# Mcontr_2.net
KiCad netlist of a schematic drawn in Altium Designer
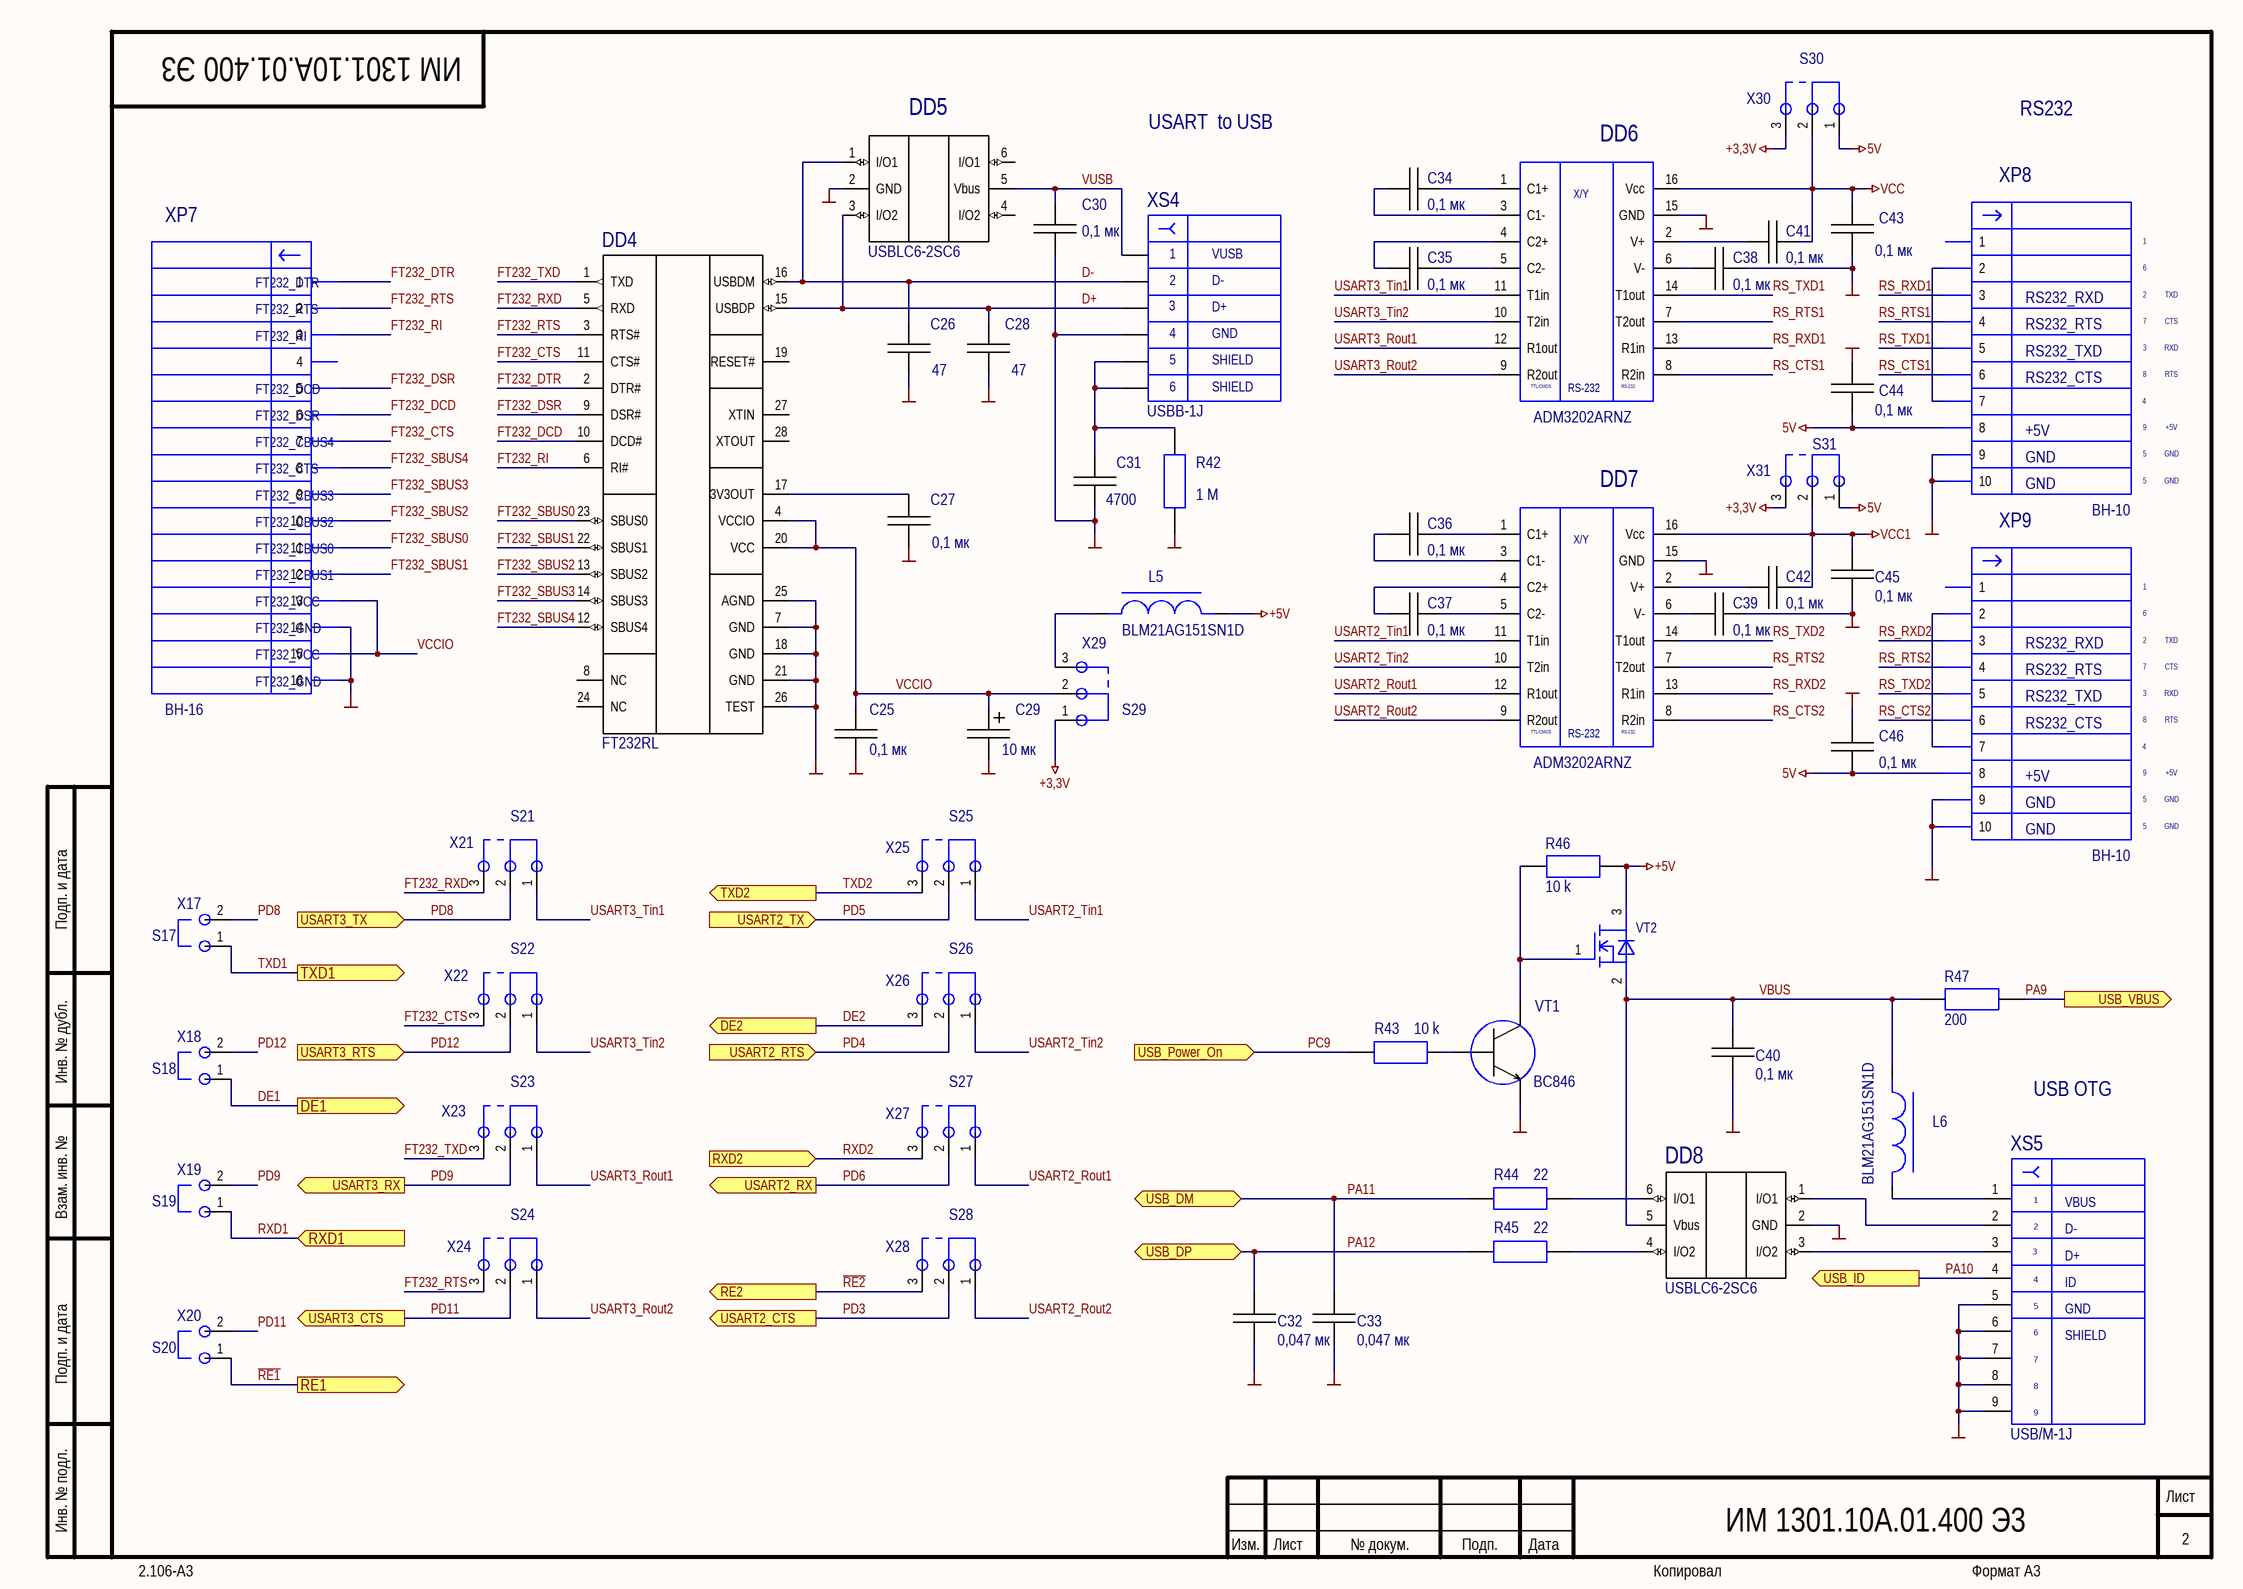
[diagram p0: Mcontr_2.SchDoc]

(export (version "E")
  (design (tool "Eeschema 10.0.6"))
  (components
    (comp (ref "C25")
      (value "0,1 мк")
      (footprint "CAPC_1206")
      (description "Capasitor")
      (fields (field (name "PART NUMBER") "C"))
      (libsource (lib "RLC_GOST") (part "C"))
    )
    (comp (ref "C26")
      (value "47")
      (footprint "CAPC_1206")
      (description "Capasitor")
      (fields (field (name "PART NUMBER") "C"))
      (libsource (lib "RLC_GOST") (part "C"))
    )
    (comp (ref "C27")
      (value "0,1 мк")
      (footprint "CAPC_1206")
      (description "Capasitor")
      (fields (field (name "PART NUMBER") "C"))
      (libsource (lib "RLC_GOST") (part "C"))
    )
    (comp (ref "C28")
      (value "47")
      (footprint "CAPC_1206")
      (description "Capasitor")
      (fields (field (name "PART NUMBER") "C"))
      (libsource (lib "RLC_GOST") (part "C"))
    )
    (comp (ref "C29")
      (value "10 мк")
      (footprint "3216")
      (description "Capasitor_polar")
      (fields (field (name "PART NUMBER") "CapPol"))
      (libsource (lib "RLC_GOST") (part "CapPol"))
    )
    (comp (ref "C30")
      (value "0,1 мк")
      (footprint "CAPC_1206")
      (description "Capasitor")
      (fields (field (name "PART NUMBER") "C"))
      (libsource (lib "RLC_GOST") (part "C"))
    )
    (comp (ref "C31")
      (value "4700")
      (footprint "CAPC_1206")
      (description "Capasitor")
      (fields (field (name "PART NUMBER") "C"))
      (libsource (lib "RLC_GOST") (part "C"))
    )
    (comp (ref "C32")
      (value "0,047 мк")
      (footprint "CAPC_1206")
      (description "Capasitor")
      (fields (field (name "PART NUMBER") "C"))
      (libsource (lib "RLC_GOST") (part "C"))
    )
    (comp (ref "C33")
      (value "0,047 мк")
      (footprint "CAPC_1206")
      (description "Capasitor")
      (fields (field (name "PART NUMBER") "C"))
      (libsource (lib "RLC_GOST") (part "C"))
    )
    (comp (ref "C34")
      (value "0,1 мк")
      (footprint "CAPC_1206")
      (description "Capasitor")
      (fields (field (name "PART NUMBER") "C"))
      (libsource (lib "RLC_GOST") (part "C"))
    )
    (comp (ref "C35")
      (value "0,1 мк")
      (footprint "CAPC_1206")
      (description "Capasitor")
      (fields (field (name "PART NUMBER") "C"))
      (libsource (lib "RLC_GOST") (part "C"))
    )
    (comp (ref "C36")
      (value "0,1 мк")
      (footprint "CAPC_1206")
      (description "Capasitor")
      (fields (field (name "PART NUMBER") "C"))
      (libsource (lib "RLC_GOST") (part "C"))
    )
    (comp (ref "C37")
      (value "0,1 мк")
      (footprint "CAPC_1206")
      (description "Capasitor")
      (fields (field (name "PART NUMBER") "C"))
      (libsource (lib "RLC_GOST") (part "C"))
    )
    (comp (ref "C38")
      (value "0,1 мк")
      (footprint "CAPC_1206")
      (description "Capasitor")
      (fields (field (name "PART NUMBER") "C"))
      (libsource (lib "RLC_GOST") (part "C"))
    )
    (comp (ref "C39")
      (value "0,1 мк")
      (footprint "CAPC_1206")
      (description "Capasitor")
      (fields (field (name "PART NUMBER") "C"))
      (libsource (lib "RLC_GOST") (part "C"))
    )
    (comp (ref "C40")
      (value "0,1 мк")
      (footprint "CAPC_1206")
      (description "Capasitor")
      (fields (field (name "PART NUMBER") "C"))
      (libsource (lib "RLC_GOST") (part "C"))
    )
    (comp (ref "C41")
      (value "0,1 мк")
      (footprint "CAPC_1206")
      (description "Capasitor")
      (fields (field (name "PART NUMBER") "C"))
      (libsource (lib "RLC_GOST") (part "C"))
    )
    (comp (ref "C42")
      (value "0,1 мк")
      (footprint "CAPC_1206")
      (description "Capasitor")
      (fields (field (name "PART NUMBER") "C"))
      (libsource (lib "RLC_GOST") (part "C"))
    )
    (comp (ref "C43")
      (value "0,1 мк")
      (footprint "CAPC_1206")
      (description "Capasitor")
      (fields (field (name "PART NUMBER") "C"))
      (libsource (lib "RLC_GOST") (part "C"))
    )
    (comp (ref "C44")
      (value "0,1 мк")
      (footprint "CAPC_1206")
      (description "Capasitor")
      (fields (field (name "PART NUMBER") "C"))
      (libsource (lib "RLC_GOST") (part "C"))
    )
    (comp (ref "C45")
      (value "0,1 мк")
      (footprint "CAPC_1206")
      (description "Capasitor")
      (fields (field (name "PART NUMBER") "C"))
      (libsource (lib "RLC_GOST") (part "C"))
    )
    (comp (ref "C46")
      (value "0,1 мк")
      (footprint "CAPC_1206")
      (description "Capasitor")
      (fields (field (name "PART NUMBER") "C"))
      (libsource (lib "RLC_GOST") (part "C"))
    )
    (comp (ref "DD4")
      (value "FT232RL")
      (footprint "SSOP28")
      (description "USB to UART interface")
      (libsource (lib "Communication transceiver") (part "FT232RL"))
    )
    (comp (ref "DD5")
      (value "USBLC6-2SC6")
      (footprint "SOT23-6L")
      (description "ESD PROTECTION")
      (libsource (lib "Diod") (part "USBLC6"))
    )
    (comp (ref "DD6")
      (value "ADM3202ARNZ")
      (footprint "SO16")
      (description "CMOS RS232 drivers/receivers")
      (libsource (lib "Communication transceiver") (part "ADM202"))
    )
    (comp (ref "DD7")
      (value "ADM3202ARNZ")
      (footprint "SO16")
      (description "CMOS RS232 drivers/receivers")
      (libsource (lib "Communication transceiver") (part "ADM202"))
    )
    (comp (ref "DD8")
      (value "USBLC6-2SC6")
      (footprint "SOT23-6L")
      (description "ESD PROTECTION")
      (libsource (lib "Diod") (part "USBLC6"))
    )
    (comp (ref "L5")
      (value "BLM21AG151SN1D")
      (footprint "C0805")
      (description "Ferrite bead")
      (libsource (lib "RLC_GOST") (part "B"))
    )
    (comp (ref "L6")
      (value "BLM21AG151SN1D")
      (footprint "C0805")
      (description "Ferrite bead")
      (libsource (lib "RLC_GOST") (part "B"))
    )
    (comp (ref "R42")
      (value "1 M")
      (footprint "SMD_1206")
      (description "Resistor,2 Pin")
      (libsource (lib "RLC_GOST") (part "R_Gost"))
    )
    (comp (ref "R43")
      (value "10 k")
      (footprint "SMD_1206")
      (description "Resistor,2 Pin")
      (libsource (lib "RLC_GOST") (part "R_Gost"))
    )
    (comp (ref "R44")
      (value "22")
      (footprint "SMD_1206")
      (description "Resistor,2 Pin")
      (libsource (lib "RLC_GOST") (part "R_Gost"))
    )
    (comp (ref "R45")
      (value "22")
      (footprint "SMD_1206")
      (description "Resistor,2 Pin")
      (libsource (lib "RLC_GOST") (part "R_Gost"))
    )
    (comp (ref "R46")
      (value "10 k")
      (footprint "SMD_1206")
      (description "Resistor,2 Pin")
      (libsource (lib "RLC_GOST") (part "R_Gost"))
    )
    (comp (ref "R47")
      (value "200")
      (footprint "SMD_1206")
      (description "Resistor,2 Pin")
      (libsource (lib "RLC_GOST") (part "R_Gost"))
    )
    (comp (ref "VT1")
      (value "BC846")
      (footprint "SOT23")
      (description "Transistor NPN Generic")
      (libsource (lib "Transistor") (part "BC846"))
    )
    (comp (ref "VT2")
      (value "IRLML2502")
      (footprint "SOT23")
      (libsource (lib "Transistor") (part "IRLML2502"))
    )
    (comp (ref "X17")
      (value "PLS-02")
      (footprint "PLS-2")
      (fields (field (name "JAMPER") "S17"))
      (libsource (lib "Connectors") (part "J2"))
    )
    (comp (ref "X18")
      (value "PLS-02")
      (footprint "PLS-2")
      (fields (field (name "JAMPER") "S18"))
      (libsource (lib "Connectors") (part "J2"))
    )
    (comp (ref "X19")
      (value "PLS-02")
      (footprint "PLS-2")
      (fields (field (name "JAMPER") "S19"))
      (libsource (lib "Connectors") (part "J2"))
    )
    (comp (ref "X20")
      (value "PLS-02")
      (footprint "PLS-2")
      (fields (field (name "JAMPER") "S20"))
      (libsource (lib "Connectors") (part "J2"))
    )
    (comp (ref "X21")
      (value "PLS-03")
      (footprint "PLS-3")
      (fields (field (name "JAMPER") "S21"))
      (libsource (lib "Connectors") (part "J3"))
    )
    (comp (ref "X22")
      (value "PLS-03")
      (footprint "PLS-3")
      (fields (field (name "JAMPER") "S22"))
      (libsource (lib "Connectors") (part "J3"))
    )
    (comp (ref "X23")
      (value "PLS-03")
      (footprint "PLS-3")
      (fields (field (name "JAMPER") "S23"))
      (libsource (lib "Connectors") (part "J3"))
    )
    (comp (ref "X24")
      (value "PLS-03")
      (footprint "PLS-3")
      (fields (field (name "JAMPER") "S24"))
      (libsource (lib "Connectors") (part "J3"))
    )
    (comp (ref "X25")
      (value "PLS-03")
      (footprint "PLS-3")
      (fields (field (name "JAMPER") "S25"))
      (libsource (lib "Connectors") (part "J3"))
    )
    (comp (ref "X26")
      (value "PLS-03")
      (footprint "PLS-3")
      (fields (field (name "JAMPER") "S26"))
      (libsource (lib "Connectors") (part "J3"))
    )
    (comp (ref "X27")
      (value "PLS-03")
      (footprint "PLS-3")
      (fields (field (name "JAMPER") "S27"))
      (libsource (lib "Connectors") (part "J3"))
    )
    (comp (ref "X28")
      (value "PLS-03")
      (footprint "PLS-3")
      (fields (field (name "JAMPER") "S28"))
      (libsource (lib "Connectors") (part "J3"))
    )
    (comp (ref "X29")
      (value "PLS-03")
      (footprint "PLS-3")
      (fields (field (name "JAMPER") "S29"))
      (libsource (lib "Connectors") (part "J3"))
    )
    (comp (ref "X30")
      (value "PLS-03")
      (footprint "PLS-3")
      (fields (field (name "JAMPER") "S30"))
      (libsource (lib "Connectors") (part "J3"))
    )
    (comp (ref "X31")
      (value "PLS-03")
      (footprint "PLS-3")
      (fields (field (name "JAMPER") "S31"))
      (libsource (lib "Connectors") (part "J3"))
    )
    (comp (ref "XP7") (value "BH-16") (footprint "PLD-16") (libsource (lib "Connectors") (part "BH-16")))
    (comp (ref "XP8") (value "BH-10") (footprint "PLD-10") (libsource (lib "Connectors") (part "BH-10")))
    (comp (ref "XP9") (value "BH-10") (footprint "PLD-10") (libsource (lib "Connectors") (part "BH-10")))
    (comp (ref "XS4") (value "USBB-1J") (footprint "USBB-1J") (libsource (lib "Connectors") (part "USBB-1J")))
    (comp (ref "XS5")
      (value "USB/M-1J")
      (footprint "MINIUSB")
      (description "9 pin connector, USB mini")
      (libsource (lib "Connectors") (part "USB/M-1J"))
    )
  )
  (nets
    (net (code "1") (name "+3,3V") (class "Default")
      (node (ref "X29") (pin "1") (pinfunction "1_1") (pintype "passive"))
      (node (ref "X30") (pin "3") (pinfunction "3_3") (pintype "passive"))
      (node (ref "X31") (pin "3") (pinfunction "3_3") (pintype "passive"))
    )
    (net (code "2") (name "+5V") (class "Default")
      (node (ref "L5") (pin "2") (pinfunction "2_2") (pintype "passive"))
      (node (ref "R46") (pin "2") (pinfunction "2_2") (pintype "passive"))
      (node (ref "VT2") (pin "3") (pinfunction "D_3") (pintype "passive"))
    )
    (net (code "3") (name "/D+") (class "Default")
      (node (ref "C28") (pin "2") (pinfunction "2_2") (pintype "passive"))
      (node (ref "DD4") (pin "15") (pinfunction "USBDP_15") (pintype "bidirectional"))
      (node (ref "DD5") (pin "3") (pinfunction "I/O2_3") (pintype "bidirectional"))
      (node (ref "XS4") (pin "3") (pintype "passive"))
    )
    (net (code "4") (name "/D-") (class "Default")
      (node (ref "C26") (pin "2") (pinfunction "2_2") (pintype "passive"))
      (node (ref "DD4") (pin "16") (pinfunction "USBDM_16") (pintype "bidirectional"))
      (node (ref "DD5") (pin "1") (pinfunction "I/O1_1") (pintype "bidirectional"))
      (node (ref "XS4") (pin "2") (pintype "passive"))
    )
    (net (code "5") (name "/DE1") (class "Default")
      (node (ref "X18") (pin "1") (pinfunction "1_1") (pintype "passive"))
    )
    (net (code "6") (name "/DE2") (class "Default")
      (node (ref "X26") (pin "3") (pinfunction "3_3") (pintype "passive"))
    )
    (net (code "7") (name "/FT232_CTS") (class "Default")
      (node (ref "DD4") (pin "11") (pinfunction "CTS#_11") (pintype "passive"))
      (node (ref "X22") (pin "3") (pinfunction "3_3") (pintype "passive"))
      (node (ref "XP7") (pin "7") (pinfunction "7_7") (pintype "passive"))
    )
    (net (code "8") (name "/FT232_DCD") (class "Default")
      (node (ref "DD4") (pin "10") (pinfunction "DCD#_10") (pintype "passive"))
      (node (ref "XP7") (pin "6") (pinfunction "6_6") (pintype "passive"))
    )
    (net (code "9") (name "/FT232_DSR") (class "Default")
      (node (ref "DD4") (pin "9") (pinfunction "DSR#_9") (pintype "passive"))
      (node (ref "XP7") (pin "5") (pinfunction "5_5") (pintype "passive"))
    )
    (net (code "10") (name "/FT232_DTR") (class "Default")
      (node (ref "DD4") (pin "2") (pinfunction "DTR#_2") (pintype "passive"))
      (node (ref "XP7") (pin "1") (pinfunction "1_1") (pintype "passive"))
    )
    (net (code "11") (name "/FT232_RI") (class "Default")
      (node (ref "DD4") (pin "6") (pinfunction "RI#_6") (pintype "passive"))
      (node (ref "XP7") (pin "3") (pinfunction "3_3") (pintype "passive"))
    )
    (net (code "12") (name "/FT232_RTS") (class "Default")
      (node (ref "DD4") (pin "3") (pinfunction "RTS#_3") (pintype "passive"))
      (node (ref "X24") (pin "3") (pinfunction "3_3") (pintype "passive"))
      (node (ref "XP7") (pin "2") (pinfunction "2_2") (pintype "passive"))
    )
    (net (code "13") (name "/FT232_RXD") (class "Default")
      (node (ref "DD4") (pin "5") (pinfunction "RXD_5") (pintype "output"))
      (node (ref "X21") (pin "3") (pinfunction "3_3") (pintype "passive"))
    )
    (net (code "14") (name "/FT232_SBUS0") (class "Default")
      (node (ref "DD4") (pin "23") (pinfunction "SBUS0_23") (pintype "bidirectional"))
      (node (ref "XP7") (pin "11") (pinfunction "11_11") (pintype "passive"))
    )
    (net (code "15") (name "/FT232_SBUS1") (class "Default")
      (node (ref "DD4") (pin "22") (pinfunction "SBUS1_22") (pintype "bidirectional"))
      (node (ref "XP7") (pin "12") (pinfunction "12_12") (pintype "passive"))
    )
    (net (code "16") (name "/FT232_SBUS2") (class "Default")
      (node (ref "DD4") (pin "13") (pinfunction "SBUS2_13") (pintype "bidirectional"))
      (node (ref "XP7") (pin "10") (pinfunction "10_10") (pintype "passive"))
    )
    (net (code "17") (name "/FT232_SBUS3") (class "Default")
      (node (ref "DD4") (pin "14") (pinfunction "SBUS3_14") (pintype "bidirectional"))
      (node (ref "XP7") (pin "9") (pinfunction "9_9") (pintype "passive"))
    )
    (net (code "18") (name "/FT232_SBUS4") (class "Default")
      (node (ref "DD4") (pin "12") (pinfunction "SBUS4_12") (pintype "bidirectional"))
      (node (ref "XP7") (pin "8") (pinfunction "8_8") (pintype "passive"))
    )
    (net (code "19") (name "/FT232_TXD") (class "Default")
      (node (ref "DD4") (pin "1") (pinfunction "TXD_1") (pintype "output"))
      (node (ref "X23") (pin "3") (pinfunction "3_3") (pintype "passive"))
    )
    (net (code "20") (name "/PA9") (class "Default")
      (node (ref "R47") (pin "2") (pinfunction "2_2") (pintype "passive"))
    )
    (net (code "21") (name "/PA10") (class "Default") (node (ref "XS5") (pin "4") (pintype "passive")))
    (net (code "22") (name "/PA11") (class "Default")
      (node (ref "C33") (pin "2") (pinfunction "2_2") (pintype "passive"))
      (node (ref "R44") (pin "2") (pinfunction "2_2") (pintype "passive"))
    )
    (net (code "23") (name "/PA12") (class "Default")
      (node (ref "C32") (pin "2") (pinfunction "2_2") (pintype "passive"))
      (node (ref "R45") (pin "2") (pinfunction "2_2") (pintype "passive"))
    )
    (net (code "24") (name "/PC9") (class "Default")
      (node (ref "R43") (pin "2") (pinfunction "2_2") (pintype "passive"))
    )
    (net (code "25") (name "/PD3") (class "Default")
      (node (ref "X28") (pin "2") (pinfunction "2_2") (pintype "passive"))
    )
    (net (code "26") (name "/PD4") (class "Default")
      (node (ref "X26") (pin "2") (pinfunction "2_2") (pintype "passive"))
    )
    (net (code "27") (name "/PD5") (class "Default")
      (node (ref "X25") (pin "2") (pinfunction "2_2") (pintype "passive"))
    )
    (net (code "28") (name "/PD6") (class "Default")
      (node (ref "X27") (pin "2") (pinfunction "2_2") (pintype "passive"))
    )
    (net (code "29") (name "/PD8") (class "Default")
      (node (ref "X17") (pin "2") (pinfunction "2_2") (pintype "passive"))
      (node (ref "X21") (pin "2") (pinfunction "2_2") (pintype "passive"))
    )
    (net (code "30") (name "/PD9") (class "Default")
      (node (ref "X19") (pin "2") (pinfunction "2_2") (pintype "passive"))
      (node (ref "X23") (pin "2") (pinfunction "2_2") (pintype "passive"))
    )
    (net (code "31") (name "/PD11") (class "Default")
      (node (ref "X20") (pin "2") (pinfunction "2_2") (pintype "passive"))
      (node (ref "X24") (pin "2") (pinfunction "2_2") (pintype "passive"))
    )
    (net (code "32") (name "/PD12") (class "Default")
      (node (ref "X18") (pin "2") (pinfunction "2_2") (pintype "passive"))
      (node (ref "X22") (pin "2") (pinfunction "2_2") (pintype "passive"))
    )
    (net (code "33") (name "/RE1") (class "Default")
      (node (ref "X20") (pin "1") (pinfunction "1_1") (pintype "passive"))
    )
    (net (code "34") (name "/RE2") (class "Default")
      (node (ref "X28") (pin "3") (pinfunction "3_3") (pintype "passive"))
    )
    (net (code "35") (name "/RS_CTS1") (class "Default")
      (node (ref "DD6") (pin "8") (pinfunction "R2in_8") (pintype "passive"))
      (node (ref "XP8") (pin "6") (pinfunction "6_6") (pintype "passive"))
    )
    (net (code "36") (name "/RS_CTS2") (class "Default")
      (node (ref "DD7") (pin "8") (pinfunction "R2in_8") (pintype "passive"))
      (node (ref "XP9") (pin "6") (pinfunction "6_6") (pintype "passive"))
    )
    (net (code "37") (name "/RS_RTS1") (class "Default")
      (node (ref "DD6") (pin "7") (pinfunction "T2out_7") (pintype "passive"))
      (node (ref "XP8") (pin "4") (pinfunction "4_4") (pintype "passive"))
    )
    (net (code "38") (name "/RS_RTS2") (class "Default")
      (node (ref "DD7") (pin "7") (pinfunction "T2out_7") (pintype "passive"))
      (node (ref "XP9") (pin "4") (pinfunction "4_4") (pintype "passive"))
    )
    (net (code "39") (name "/RS_RXD1") (class "Default")
      (node (ref "DD6") (pin "13") (pinfunction "R1in_13") (pintype "passive"))
      (node (ref "XP8") (pin "3") (pinfunction "3_3") (pintype "passive"))
    )
    (net (code "40") (name "/RS_RXD2") (class "Default")
      (node (ref "DD7") (pin "13") (pinfunction "R1in_13") (pintype "passive"))
      (node (ref "XP9") (pin "3") (pinfunction "3_3") (pintype "passive"))
    )
    (net (code "41") (name "/RS_TXD1") (class "Default")
      (node (ref "DD6") (pin "14") (pinfunction "T1out_14") (pintype "passive"))
      (node (ref "XP8") (pin "5") (pinfunction "5_5") (pintype "passive"))
    )
    (net (code "42") (name "/RS_TXD2") (class "Default")
      (node (ref "DD7") (pin "14") (pinfunction "T1out_14") (pintype "passive"))
      (node (ref "XP9") (pin "5") (pinfunction "5_5") (pintype "passive"))
    )
    (net (code "43") (name "/RXD1") (class "Default")
      (node (ref "X19") (pin "1") (pinfunction "1_1") (pintype "passive"))
    )
    (net (code "44") (name "/RXD2") (class "Default")
      (node (ref "X27") (pin "3") (pinfunction "3_3") (pintype "passive"))
    )
    (net (code "45") (name "/TXD1") (class "Default")
      (node (ref "X17") (pin "1") (pinfunction "1_1") (pintype "passive"))
    )
    (net (code "46") (name "/TXD2") (class "Default")
      (node (ref "X25") (pin "3") (pinfunction "3_3") (pintype "passive"))
    )
    (net (code "47") (name "/USART2_Rout1") (class "Default")
      (node (ref "DD7") (pin "12") (pinfunction "R1out_12") (pintype "passive"))
      (node (ref "X27") (pin "1") (pinfunction "1_1") (pintype "passive"))
    )
    (net (code "48") (name "/USART2_Rout2") (class "Default")
      (node (ref "DD7") (pin "9") (pinfunction "R2out_9") (pintype "passive"))
      (node (ref "X28") (pin "1") (pinfunction "1_1") (pintype "passive"))
    )
    (net (code "49") (name "/USART2_Tin1") (class "Default")
      (node (ref "DD7") (pin "11") (pinfunction "T1in_11") (pintype "passive"))
      (node (ref "X25") (pin "1") (pinfunction "1_1") (pintype "passive"))
    )
    (net (code "50") (name "/USART2_Tin2") (class "Default")
      (node (ref "DD7") (pin "10") (pinfunction "T2in_10") (pintype "passive"))
      (node (ref "X26") (pin "1") (pinfunction "1_1") (pintype "passive"))
    )
    (net (code "51") (name "/USART3_Rout1") (class "Default")
      (node (ref "DD6") (pin "12") (pinfunction "R1out_12") (pintype "passive"))
      (node (ref "X23") (pin "1") (pinfunction "1_1") (pintype "passive"))
    )
    (net (code "52") (name "/USART3_Rout2") (class "Default")
      (node (ref "DD6") (pin "9") (pinfunction "R2out_9") (pintype "passive"))
      (node (ref "X24") (pin "1") (pinfunction "1_1") (pintype "passive"))
    )
    (net (code "53") (name "/USART3_Tin1") (class "Default")
      (node (ref "DD6") (pin "11") (pinfunction "T1in_11") (pintype "passive"))
      (node (ref "X21") (pin "1") (pinfunction "1_1") (pintype "passive"))
    )
    (net (code "54") (name "/USART3_Tin2") (class "Default")
      (node (ref "DD6") (pin "10") (pinfunction "T2in_10") (pintype "passive"))
      (node (ref "X22") (pin "1") (pinfunction "1_1") (pintype "passive"))
    )
    (net (code "55") (name "/VBUS") (class "Default")
      (node (ref "C40") (pin "2") (pinfunction "2_2") (pintype "passive"))
      (node (ref "DD8") (pin "5") (pinfunction "Vbus_5") (pintype "power_in"))
      (node (ref "L6") (pin "1") (pinfunction "1_1") (pintype "passive"))
      (node (ref "R47") (pin "1") (pinfunction "1_1") (pintype "passive"))
      (node (ref "VT2") (pin "2") (pinfunction "S_2") (pintype "passive"))
    )
    (net (code "56") (name "/VCCIO") (class "Default")
      (node (ref "C25") (pin "2") (pinfunction "2_2") (pintype "passive"))
      (node (ref "C29") (pin "1") (pinfunction "+_1") (pintype "passive"))
      (node (ref "DD4") (pin "20") (pinfunction "VCC_20") (pintype "power_in"))
      (node (ref "DD4") (pin "4") (pinfunction "VCCIO_4") (pintype "power_in"))
      (node (ref "X29") (pin "2") (pinfunction "2_2") (pintype "passive"))
      (node (ref "XP7") (pin "13") (pinfunction "13_13") (pintype "passive"))
      (node (ref "XP7") (pin "15") (pinfunction "15_15") (pintype "passive"))
    )
    (net (code "57") (name "/VUSB") (class "Default")
      (node (ref "C30") (pin "2") (pinfunction "2_2") (pintype "passive"))
      (node (ref "DD5") (pin "5") (pinfunction "Vbus_5") (pintype "power_in"))
      (node (ref "XS4") (pin "1") (pintype "passive"))
    )
    (net (code "58") (name "5V") (class "Default")
      (node (ref "C44") (pin "1") (pinfunction "1_1") (pintype "passive"))
      (node (ref "C46") (pin "1") (pinfunction "1_1") (pintype "passive"))
      (node (ref "X30") (pin "1") (pinfunction "1_1") (pintype "passive"))
      (node (ref "X31") (pin "1") (pinfunction "1_1") (pintype "passive"))
      (node (ref "XP8") (pin "8") (pinfunction "8_8") (pintype "passive"))
      (node (ref "XP9") (pin "8") (pinfunction "8_8") (pintype "passive"))
    )
    (net (code "59") (name "GND") (class "Default")
      (node (ref "C25") (pin "1") (pinfunction "1_1") (pintype "passive"))
      (node (ref "C26") (pin "1") (pinfunction "1_1") (pintype "passive"))
      (node (ref "C27") (pin "1") (pinfunction "1_1") (pintype "passive"))
      (node (ref "C28") (pin "1") (pinfunction "1_1") (pintype "passive"))
      (node (ref "C29") (pin "2") (pinfunction "-_2") (pintype "passive"))
      (node (ref "C30") (pin "1") (pinfunction "1_1") (pintype "passive"))
      (node (ref "C31") (pin "1") (pinfunction "1_1") (pintype "passive"))
      (node (ref "C32") (pin "1") (pinfunction "1_1") (pintype "passive"))
      (node (ref "C33") (pin "1") (pinfunction "1_1") (pintype "passive"))
      (node (ref "C38") (pin "2") (pinfunction "2_2") (pintype "passive"))
      (node (ref "C39") (pin "2") (pinfunction "2_2") (pintype "passive"))
      (node (ref "C40") (pin "1") (pinfunction "1_1") (pintype "passive"))
      (node (ref "C43") (pin "1") (pinfunction "1_1") (pintype "passive"))
      (node (ref "C44") (pin "2") (pinfunction "2_2") (pintype "passive"))
      (node (ref "C45") (pin "1") (pinfunction "1_1") (pintype "passive"))
      (node (ref "C46") (pin "2") (pinfunction "2_2") (pintype "passive"))
      (node (ref "DD4") (pin "18") (pinfunction "GND_18") (pintype "power_in"))
      (node (ref "DD4") (pin "21") (pinfunction "GND_21") (pintype "power_in"))
      (node (ref "DD4") (pin "25") (pinfunction "AGND_25") (pintype "power_in"))
      (node (ref "DD4") (pin "26") (pinfunction "TEST_26") (pintype "passive"))
      (node (ref "DD4") (pin "7") (pinfunction "GND_7") (pintype "power_in"))
      (node (ref "DD5") (pin "2") (pinfunction "GND_2") (pintype "power_in"))
      (node (ref "DD6") (pin "15") (pinfunction "GND_15") (pintype "passive"))
      (node (ref "DD7") (pin "15") (pinfunction "GND_15") (pintype "passive"))
      (node (ref "DD8") (pin "2") (pinfunction "GND_2") (pintype "power_in"))
      (node (ref "R42") (pin "1") (pinfunction "1_1") (pintype "passive"))
      (node (ref "VT1") (pin "2") (pinfunction "E_2") (pintype "passive"))
      (node (ref "XP7") (pin "14") (pinfunction "14_14") (pintype "passive"))
      (node (ref "XP7") (pin "16") (pinfunction "16_16") (pintype "passive"))
      (node (ref "XP8") (pin "10") (pinfunction "10_10") (pintype "passive"))
      (node (ref "XP8") (pin "9") (pinfunction "9_9") (pintype "passive"))
      (node (ref "XP9") (pin "10") (pinfunction "10_10") (pintype "passive"))
      (node (ref "XP9") (pin "9") (pinfunction "9_9") (pintype "passive"))
      (node (ref "XS4") (pin "4") (pintype "passive"))
      (node (ref "XS5") (pin "5") (pintype "passive"))
      (node (ref "XS5") (pin "6") (pintype "passive"))
      (node (ref "XS5") (pin "7") (pintype "passive"))
      (node (ref "XS5") (pin "8") (pintype "passive"))
      (node (ref "XS5") (pin "9") (pintype "passive"))
    )
    (net (code "60") (name "Net-(C31-Pad2)") (class "Default")
      (node (ref "C31") (pin "2") (pinfunction "2_2") (pintype "passive"))
      (node (ref "R42") (pin "2") (pinfunction "2_2") (pintype "passive"))
      (node (ref "XS4") (pin "5") (pintype "passive"))
      (node (ref "XS4") (pin "6") (pintype "passive"))
    )
    (net (code "61") (name "Net-(DD4-3V3OUT)") (class "Default")
      (node (ref "C27") (pin "2") (pinfunction "2_2") (pintype "passive"))
      (node (ref "DD4") (pin "17") (pinfunction "3V3OUT_17") (pintype "power_in"))
    )
    (net (code "62") (name "Net-(DD6-C1+)") (class "Default")
      (node (ref "C34") (pin "2") (pinfunction "2_2") (pintype "passive"))
      (node (ref "DD6") (pin "1") (pinfunction "C1+_1") (pintype "passive"))
    )
    (net (code "63") (name "Net-(DD6-C1-)") (class "Default")
      (node (ref "C34") (pin "1") (pinfunction "1_1") (pintype "passive"))
      (node (ref "DD6") (pin "3") (pinfunction "C1-_3") (pintype "passive"))
    )
    (net (code "64") (name "Net-(DD6-C2+)") (class "Default")
      (node (ref "C35") (pin "1") (pinfunction "1_1") (pintype "passive"))
      (node (ref "DD6") (pin "4") (pinfunction "C2+_4") (pintype "passive"))
    )
    (net (code "65") (name "Net-(DD6-C2-)") (class "Default")
      (node (ref "C35") (pin "2") (pinfunction "2_2") (pintype "passive"))
      (node (ref "DD6") (pin "5") (pinfunction "C2-_5") (pintype "passive"))
    )
    (net (code "66") (name "Net-(DD6-V+)") (class "Default")
      (node (ref "C41") (pin "1") (pinfunction "1_1") (pintype "passive"))
      (node (ref "DD6") (pin "2") (pinfunction "V+_2") (pintype "passive"))
    )
    (net (code "67") (name "Net-(DD6-V-)") (class "Default")
      (node (ref "C38") (pin "1") (pinfunction "1_1") (pintype "passive"))
      (node (ref "DD6") (pin "6") (pinfunction "V-_6") (pintype "passive"))
    )
    (net (code "68") (name "Net-(DD7-C1+)") (class "Default")
      (node (ref "C36") (pin "2") (pinfunction "2_2") (pintype "passive"))
      (node (ref "DD7") (pin "1") (pinfunction "C1+_1") (pintype "passive"))
    )
    (net (code "69") (name "Net-(DD7-C1-)") (class "Default")
      (node (ref "C36") (pin "1") (pinfunction "1_1") (pintype "passive"))
      (node (ref "DD7") (pin "3") (pinfunction "C1-_3") (pintype "passive"))
    )
    (net (code "70") (name "Net-(DD7-C2+)") (class "Default")
      (node (ref "C37") (pin "1") (pinfunction "1_1") (pintype "passive"))
      (node (ref "DD7") (pin "4") (pinfunction "C2+_4") (pintype "passive"))
    )
    (net (code "71") (name "Net-(DD7-C2-)") (class "Default")
      (node (ref "C37") (pin "2") (pinfunction "2_2") (pintype "passive"))
      (node (ref "DD7") (pin "5") (pinfunction "C2-_5") (pintype "passive"))
    )
    (net (code "72") (name "Net-(DD7-V+)") (class "Default")
      (node (ref "C42") (pin "1") (pinfunction "1_1") (pintype "passive"))
      (node (ref "DD7") (pin "2") (pinfunction "V+_2") (pintype "passive"))
    )
    (net (code "73") (name "Net-(DD7-V-)") (class "Default")
      (node (ref "C39") (pin "1") (pinfunction "1_1") (pintype "passive"))
      (node (ref "DD7") (pin "6") (pinfunction "V-_6") (pintype "passive"))
    )
    (net (code "74") (name "Net-(DD8-I{slash}O1-Pad1)") (class "Default")
      (node (ref "DD8") (pin "1") (pinfunction "I/O1_1") (pintype "bidirectional"))
      (node (ref "XS5") (pin "2") (pintype "passive"))
    )
    (net (code "75") (name "Net-(DD8-I{slash}O1-Pad6)") (class "Default")
      (node (ref "DD8") (pin "6") (pinfunction "I/O1_6") (pintype "bidirectional"))
      (node (ref "R44") (pin "1") (pinfunction "1_1") (pintype "passive"))
    )
    (net (code "76") (name "Net-(DD8-I{slash}O2-Pad3)") (class "Default")
      (node (ref "DD8") (pin "3") (pinfunction "I/O2_3") (pintype "bidirectional"))
      (node (ref "XS5") (pin "3") (pintype "passive"))
    )
    (net (code "77") (name "Net-(DD8-I{slash}O2-Pad4)") (class "Default")
      (node (ref "DD8") (pin "4") (pinfunction "I/O2_4") (pintype "bidirectional"))
      (node (ref "R45") (pin "1") (pinfunction "1_1") (pintype "passive"))
    )
    (net (code "78") (name "Net-(L5-Pad1)") (class "Default")
      (node (ref "L5") (pin "1") (pinfunction "1_1") (pintype "passive"))
      (node (ref "X29") (pin "3") (pinfunction "3_3") (pintype "passive"))
    )
    (net (code "79") (name "Net-(L6-Pad2)") (class "Default")
      (node (ref "L6") (pin "2") (pinfunction "2_2") (pintype "passive"))
      (node (ref "XS5") (pin "1") (pintype "passive"))
    )
    (net (code "80") (name "Net-(VT1-B)") (class "Default")
      (node (ref "R43") (pin "1") (pinfunction "1_1") (pintype "passive"))
      (node (ref "VT1") (pin "1") (pinfunction "B_1") (pintype "passive"))
    )
    (net (code "81") (name "Net-(VT1-K)") (class "Default")
      (node (ref "R46") (pin "1") (pinfunction "1_1") (pintype "passive"))
      (node (ref "VT1") (pin "3") (pinfunction "K_3") (pintype "passive"))
      (node (ref "VT2") (pin "1") (pinfunction "G_1") (pintype "passive"))
    )
    (net (code "82") (name "Net-(XP8-Pad2)") (class "Default")
      (node (ref "XP8") (pin "2") (pinfunction "2_2") (pintype "passive"))
      (node (ref "XP8") (pin "7") (pinfunction "7_7") (pintype "passive"))
    )
    (net (code "83") (name "Net-(XP9-Pad2)") (class "Default")
      (node (ref "XP9") (pin "2") (pinfunction "2_2") (pintype "passive"))
      (node (ref "XP9") (pin "7") (pinfunction "7_7") (pintype "passive"))
    )
    (net (code "84") (name "VCC") (class "Default")
      (node (ref "C41") (pin "2") (pinfunction "2_2") (pintype "passive"))
      (node (ref "C43") (pin "2") (pinfunction "2_2") (pintype "passive"))
      (node (ref "DD6") (pin "16") (pinfunction "Vcc_16") (pintype "passive"))
      (node (ref "X30") (pin "2") (pinfunction "2_2") (pintype "passive"))
    )
    (net (code "85") (name "VCC1") (class "Default")
      (node (ref "C42") (pin "2") (pinfunction "2_2") (pintype "passive"))
      (node (ref "C45") (pin "2") (pinfunction "2_2") (pintype "passive"))
      (node (ref "DD7") (pin "16") (pinfunction "Vcc_16") (pintype "passive"))
      (node (ref "X31") (pin "2") (pinfunction "2_2") (pintype "passive"))
    )
    (net (code "86") (name "unconnected-(DD4-NC-Pad8)") (class "Default")
      (node (ref "DD4") (pin "8") (pinfunction "NC_8") (pintype "passive"))
    )
    (net (code "87") (name "unconnected-(DD4-NC-Pad24)") (class "Default")
      (node (ref "DD4") (pin "24") (pinfunction "NC_24") (pintype "passive"))
    )
    (net (code "88") (name "unconnected-(DD4-RESET#-Pad19)") (class "Default")
      (node (ref "DD4") (pin "19") (pinfunction "RESET#_19") (pintype "passive"))
    )
    (net (code "89") (name "unconnected-(DD4-XTIN-Pad27)") (class "Default")
      (node (ref "DD4") (pin "27") (pinfunction "XTIN_27") (pintype "passive"))
    )
    (net (code "90") (name "unconnected-(DD4-XTOUT-Pad28)") (class "Default")
      (node (ref "DD4") (pin "28") (pinfunction "XTOUT_28") (pintype "passive"))
    )
    (net (code "91") (name "unconnected-(DD5-I{slash}O1-Pad6)") (class "Default")
      (node (ref "DD5") (pin "6") (pinfunction "I/O1_6") (pintype "bidirectional"))
    )
    (net (code "92") (name "unconnected-(DD5-I{slash}O2-Pad4)") (class "Default")
      (node (ref "DD5") (pin "4") (pinfunction "I/O2_4") (pintype "bidirectional"))
    )
    (net (code "93") (name "unconnected-(XP7-Pad4)") (class "Default")
      (node (ref "XP7") (pin "4") (pinfunction "4_4") (pintype "passive"))
    )
    (net (code "94") (name "unconnected-(XP8-Pad1)") (class "Default")
      (node (ref "XP8") (pin "1") (pinfunction "1_1") (pintype "passive"))
    )
    (net (code "95") (name "unconnected-(XP9-Pad1)") (class "Default")
      (node (ref "XP9") (pin "1") (pinfunction "1_1") (pintype "passive"))
    )
  )
)
